# SerLCD.net
KiCad netlist of a schematic drawn in EAGLE
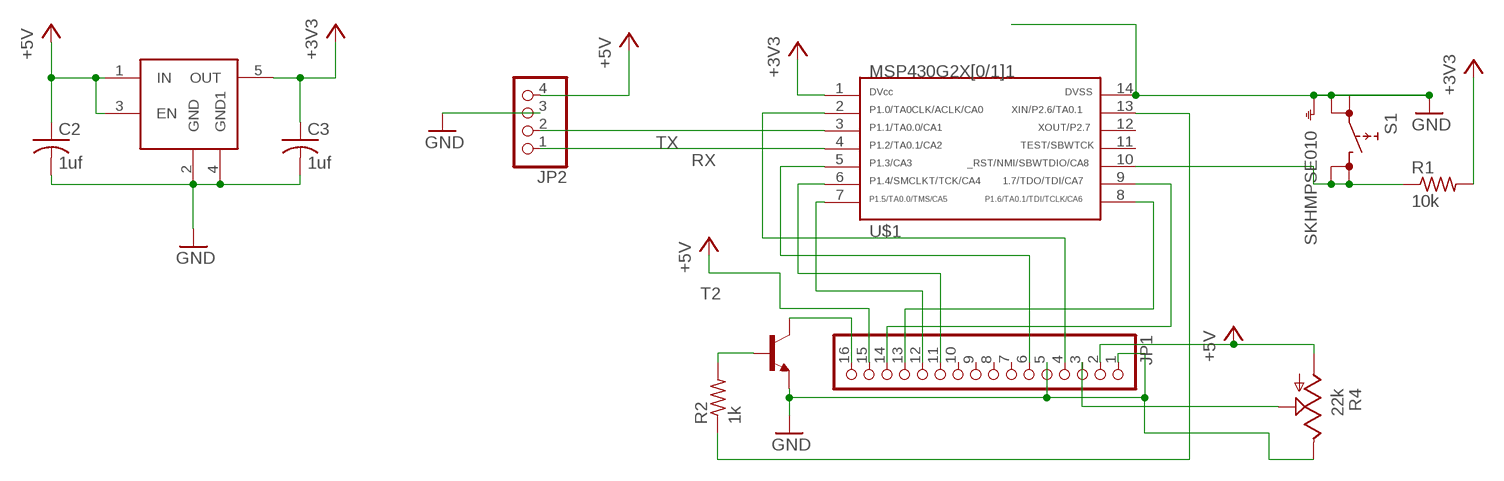
[diagram p0: schematic, sheet 1]

(export (version "E")
  (design (tool "Eeschema 10.0.6"))
  (components
    (comp (ref "C2")
      (value "1uf")
      (footprint "eagle-import:C025-025X050")
      (libsource (lib "eagle-import") (part "C-US025-025X050"))
    )
    (comp (ref "C3")
      (value "1uf")
      (footprint "eagle-import:C025-025X050")
      (libsource (lib "eagle-import") (part "C-US025-025X050"))
    )
    (comp (ref "JP1")
      (value "PINHD-1X16")
      (footprint "eagle-import:1X16")
      (libsource (lib "eagle-import") (part "PINHD-1X16"))
    )
    (comp (ref "JP2")
      (value "PINHD-1X4")
      (footprint "eagle-import:1X04")
      (libsource (lib "eagle-import") (part "PINHD-1X4"))
    )
    (comp (ref "R1")
      (value "10k")
      (footprint "eagle-import:0207_10")
      (libsource (lib "eagle-import") (part "R-US_0207/10"))
    )
    (comp (ref "R2")
      (value "1k")
      (footprint "eagle-import:0207_10")
      (libsource (lib "eagle-import") (part "R-US_0207/10"))
    )
    (comp (ref "R4")
      (value "22k")
      (footprint "eagle-import:CA6H")
      (libsource (lib "eagle-import") (part "TRIM_US-CA6H"))
    )
    (comp (ref "S1")
      (value "SKHMPSE010")
      (footprint "eagle-import:SKHMPXE010")
      (libsource (lib "eagle-import") (part "SKHMPE010S"))
    )
    (comp (ref "T2")
      (value "-NPN-TO92-EBC")
      (footprint "eagle-import:TO92-EBC")
      (libsource (lib "eagle-import") (part "-NPN-TO92-EBC"))
    )
    (comp (ref "U$1")
      (value "G2X[0/1]1---N14")
      (footprint "eagle-import:N14")
      (libsource (lib "eagle-import") (part "G2X[0/1]1---N14"))
    )
    (comp (ref "U$2")
      (value "TPS783XX")
      (footprint "eagle-import:DBV-R-PDSO-G5")
      (libsource (lib "eagle-import") (part "TPS783XX"))
    )
  )
  (nets
    (net (code "1") (name "+3V3") (class "Default")
      (node (ref "C3") (pin "1") (pinfunction "1_1") (pintype "passive"))
      (node (ref "R1") (pin "2") (pinfunction "2_2") (pintype "passive"))
      (node (ref "U$1") (pin "1") (pinfunction "1_1") (pintype "bidirectional"))
      (node (ref "U$2") (pin "5") (pinfunction "OUT_5") (pintype "bidirectional"))
    )
    (net (code "2") (name "+5V") (class "Default")
      (node (ref "C2") (pin "1") (pinfunction "1_1") (pintype "passive"))
      (node (ref "JP1") (pin "15") (pinfunction "15_15") (pintype "passive"))
      (node (ref "JP1") (pin "2") (pinfunction "2_2") (pintype "passive"))
      (node (ref "JP2") (pin "4") (pinfunction "4_4") (pintype "passive"))
      (node (ref "R4") (pin "A") (pinfunction "A_A") (pintype "passive"))
      (node (ref "U$2") (pin "1") (pinfunction "IN_1") (pintype "bidirectional"))
      (node (ref "U$2") (pin "3") (pinfunction "EN_3") (pintype "bidirectional"))
    )
    (net (code "3") (name "/RX") (class "Default")
      (node (ref "JP2") (pin "1") (pinfunction "1_1") (pintype "passive"))
      (node (ref "U$1") (pin "4") (pinfunction "4_4") (pintype "bidirectional"))
    )
    (net (code "4") (name "/TX") (class "Default")
      (node (ref "JP2") (pin "2") (pinfunction "2_2") (pintype "passive"))
      (node (ref "U$1") (pin "3") (pinfunction "3_3") (pintype "bidirectional"))
    )
    (net (code "5") (name "GND") (class "Default")
      (node (ref "C2") (pin "2") (pinfunction "2_2") (pintype "passive"))
      (node (ref "C3") (pin "2") (pinfunction "2_2") (pintype "passive"))
      (node (ref "JP1") (pin "1") (pinfunction "1_1") (pintype "passive"))
      (node (ref "JP1") (pin "5") (pinfunction "5_5") (pintype "passive"))
      (node (ref "JP2") (pin "3") (pinfunction "3_3") (pintype "passive"))
      (node (ref "R4") (pin "E") (pinfunction "E_E") (pintype "passive"))
      (node (ref "S1") (pin "1") (pinfunction "1.1_1") (pintype "passive"))
      (node (ref "S1") (pin "2") (pinfunction "1.2_2") (pintype "passive"))
      (node (ref "S1") (pin "5") (pinfunction "SH_5") (pintype "passive"))
      (node (ref "T2") (pin "E") (pinfunction "E_E") (pintype "passive"))
      (node (ref "U$1") (pin "14") (pinfunction "14_14") (pintype "bidirectional"))
      (node (ref "U$2") (pin "2") (pinfunction "GND_2") (pintype "bidirectional"))
      (node (ref "U$2") (pin "4") (pinfunction "GND1_4") (pintype "bidirectional"))
    )
    (net (code "6") (name "Net-(JP1-Pad3)") (class "Default")
      (node (ref "JP1") (pin "3") (pinfunction "3_3") (pintype "passive"))
      (node (ref "R4") (pin "S") (pinfunction "S_S") (pintype "passive"))
    )
    (net (code "7") (name "Net-(JP1-Pad4)") (class "Default")
      (node (ref "JP1") (pin "4") (pinfunction "4_4") (pintype "passive"))
      (node (ref "U$1") (pin "2") (pinfunction "2_2") (pintype "bidirectional"))
    )
    (net (code "8") (name "Net-(JP1-Pad6)") (class "Default")
      (node (ref "JP1") (pin "6") (pinfunction "6_6") (pintype "passive"))
      (node (ref "U$1") (pin "5") (pinfunction "5_5") (pintype "bidirectional"))
    )
    (net (code "9") (name "Net-(JP1-Pad11)") (class "Default")
      (node (ref "JP1") (pin "11") (pinfunction "11_11") (pintype "passive"))
      (node (ref "U$1") (pin "6") (pinfunction "6_6") (pintype "bidirectional"))
    )
    (net (code "10") (name "Net-(JP1-Pad12)") (class "Default")
      (node (ref "JP1") (pin "12") (pinfunction "12_12") (pintype "passive"))
      (node (ref "U$1") (pin "7") (pinfunction "7_7") (pintype "bidirectional"))
    )
    (net (code "11") (name "Net-(JP1-Pad13)") (class "Default")
      (node (ref "JP1") (pin "13") (pinfunction "13_13") (pintype "passive"))
      (node (ref "U$1") (pin "8") (pinfunction "8_8") (pintype "bidirectional"))
    )
    (net (code "12") (name "Net-(JP1-Pad14)") (class "Default")
      (node (ref "JP1") (pin "14") (pinfunction "14_14") (pintype "passive"))
      (node (ref "U$1") (pin "9") (pinfunction "9_9") (pintype "bidirectional"))
    )
    (net (code "13") (name "Net-(JP1-Pad16)") (class "Default")
      (node (ref "JP1") (pin "16") (pinfunction "16_16") (pintype "passive"))
      (node (ref "T2") (pin "C") (pinfunction "C_C") (pintype "passive"))
    )
    (net (code "14") (name "Net-(R2-Pad1)") (class "Default")
      (node (ref "R2") (pin "1") (pinfunction "1_1") (pintype "passive"))
      (node (ref "U$1") (pin "13") (pinfunction "13_13") (pintype "bidirectional"))
    )
    (net (code "15") (name "Net-(R2-Pad2)") (class "Default")
      (node (ref "R2") (pin "2") (pinfunction "2_2") (pintype "passive"))
      (node (ref "T2") (pin "B") (pinfunction "B_B") (pintype "passive"))
    )
    (net (code "16") (name "Net-(S1-2.1)") (class "Default")
      (node (ref "R1") (pin "1") (pinfunction "1_1") (pintype "passive"))
      (node (ref "S1") (pin "3") (pinfunction "2.1_3") (pintype "passive"))
      (node (ref "S1") (pin "4") (pinfunction "2.2_4") (pintype "passive"))
      (node (ref "U$1") (pin "10") (pinfunction "10_10") (pintype "bidirectional"))
    )
    (net (code "17") (name "unconnected-(JP1-Pad7)") (class "Default")
      (node (ref "JP1") (pin "7") (pinfunction "7_7") (pintype "passive"))
    )
    (net (code "18") (name "unconnected-(JP1-Pad8)") (class "Default")
      (node (ref "JP1") (pin "8") (pinfunction "8_8") (pintype "passive"))
    )
    (net (code "19") (name "unconnected-(JP1-Pad9)") (class "Default")
      (node (ref "JP1") (pin "9") (pinfunction "9_9") (pintype "passive"))
    )
    (net (code "20") (name "unconnected-(JP1-Pad10)") (class "Default")
      (node (ref "JP1") (pin "10") (pinfunction "10_10") (pintype "passive"))
    )
    (net (code "21") (name "unconnected-(U$1-Pad11)") (class "Default")
      (node (ref "U$1") (pin "11") (pinfunction "11_11") (pintype "bidirectional"))
    )
    (net (code "22") (name "unconnected-(U$1-Pad12)") (class "Default")
      (node (ref "U$1") (pin "12") (pinfunction "12_12") (pintype "bidirectional"))
    )
  )
)
